# Circuit_Serial_3.net
KiCad netlist of a schematic drawn in EAGLE
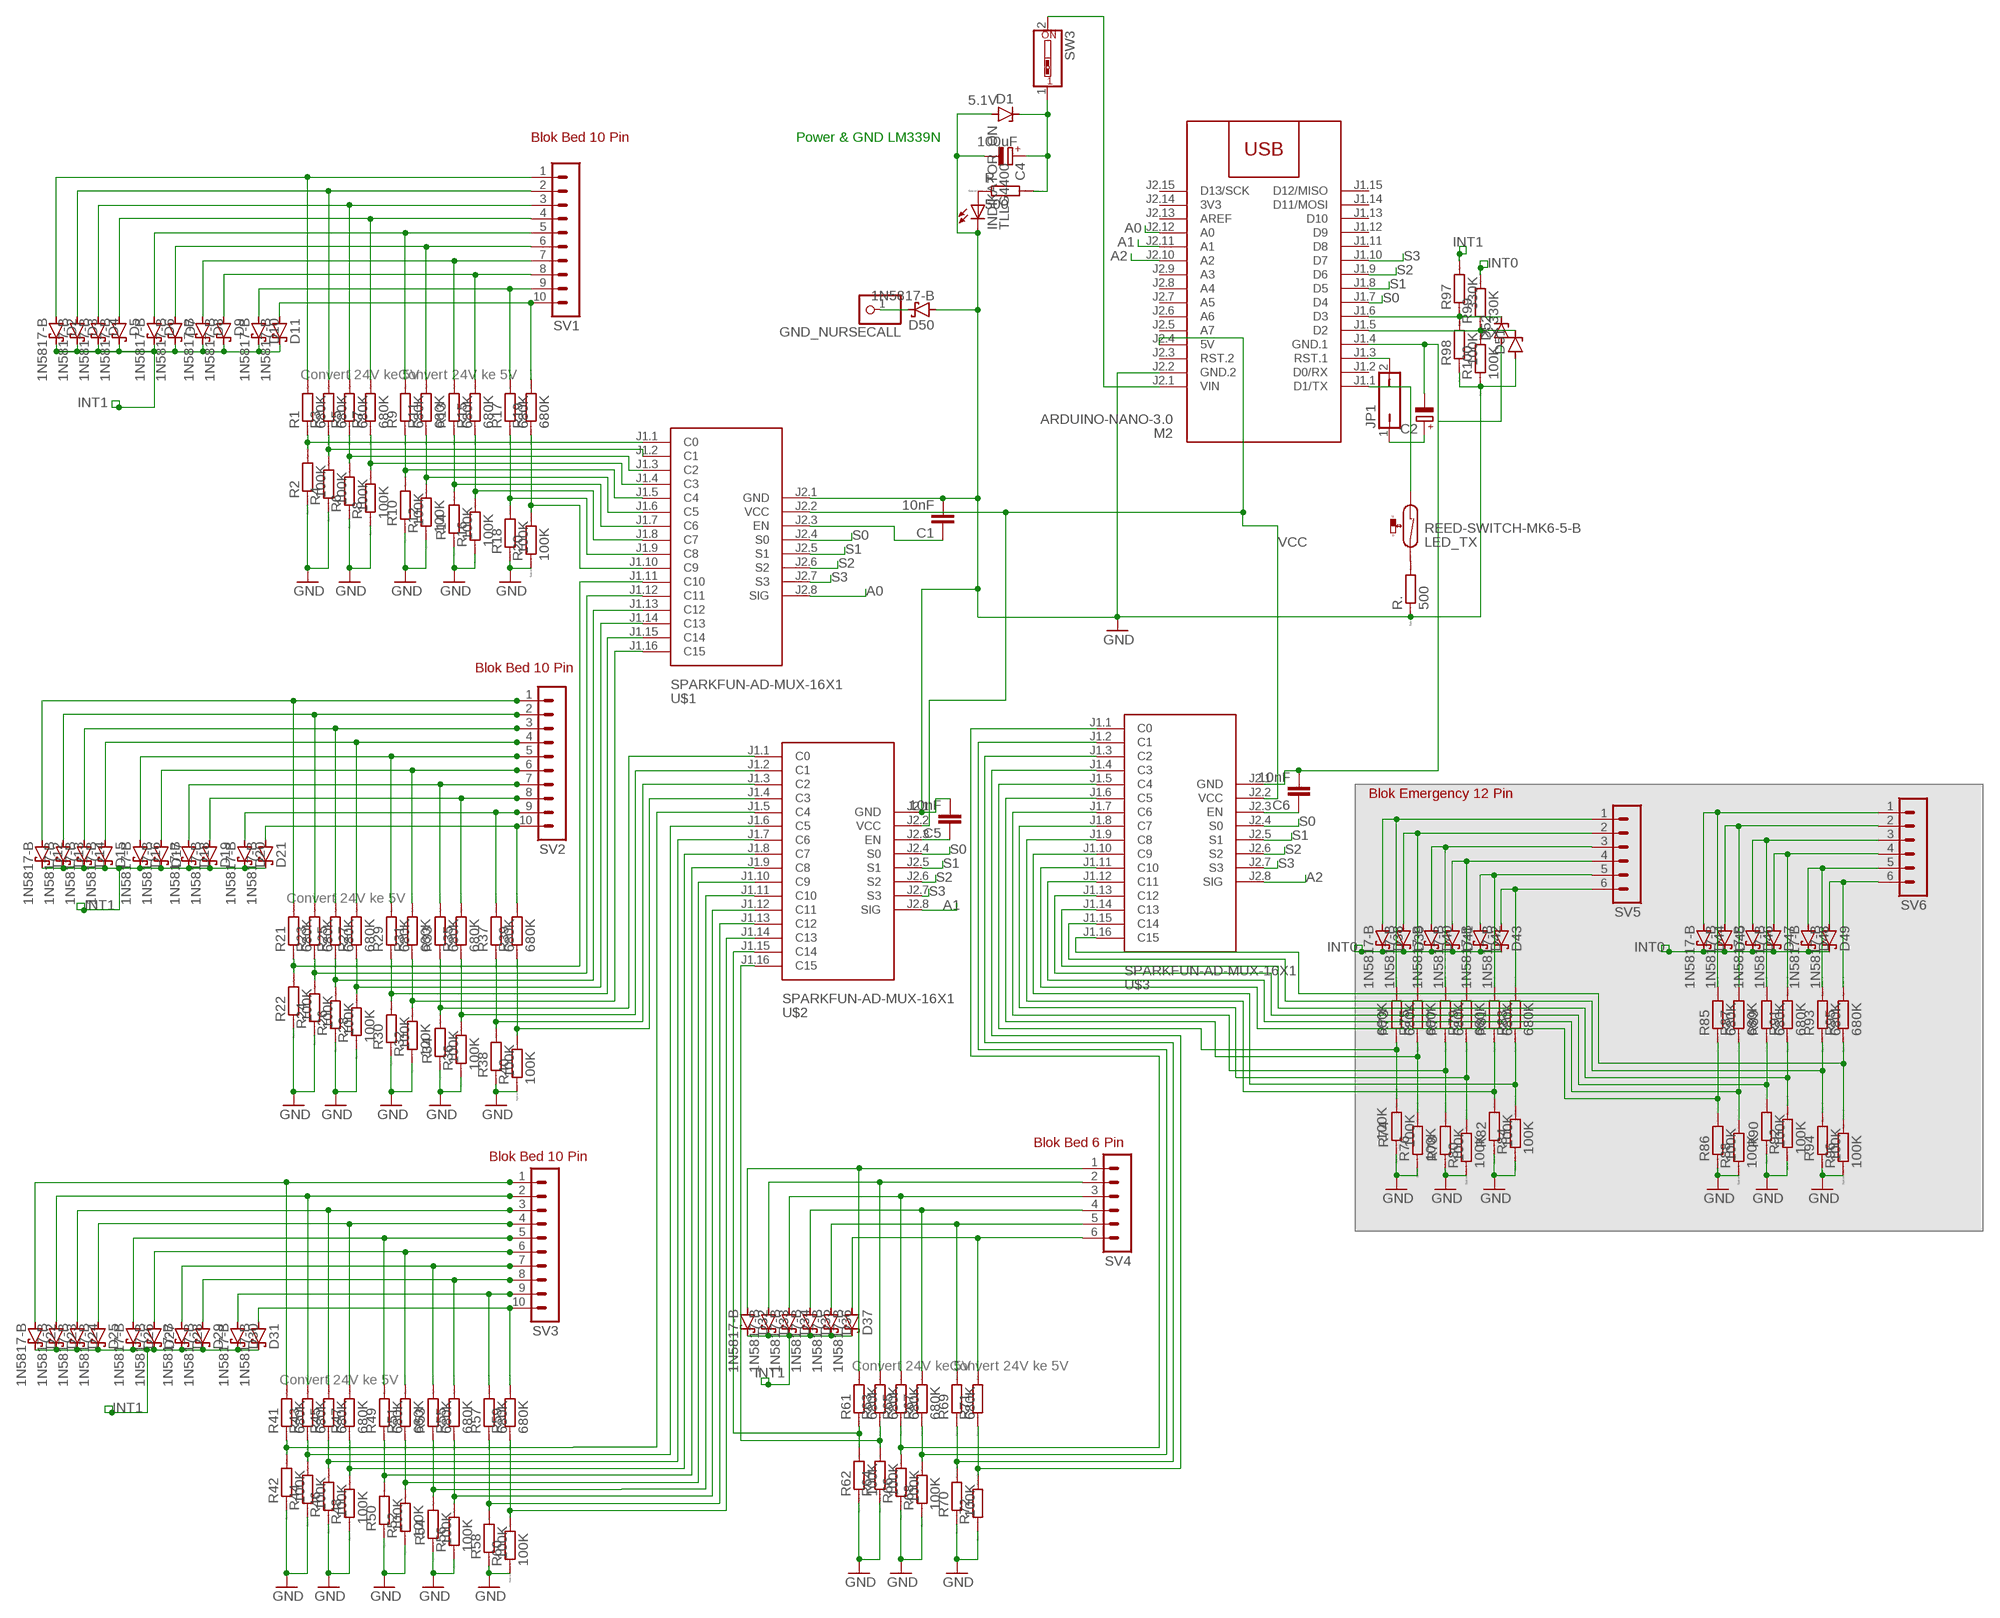
[diagram p0: schematic, sheet 1]

(export (version "E")
  (design (tool "Eeschema 10.0.6"))
  (components
    (comp (ref "C1")
      (value "10nF")
      (footprint "eagle-import:C025-030X050")
      (libsource (lib "eagle-import") (part "C-EU025-030X050"))
    )
    (comp (ref "C2")
      (value "CPOL-EUE3.5-8")
      (footprint "eagle-import:E3,5-8")
      (libsource (lib "eagle-import") (part "CPOL-EUE3.5-8"))
    )
    (comp (ref "C4")
      (value "100uF")
      (footprint "eagle-import:E3,5-10")
      (libsource (lib "eagle-import") (part "CPOL-EUE3.5-10"))
    )
    (comp (ref "C5")
      (value "10nF")
      (footprint "eagle-import:C025-030X050")
      (libsource (lib "eagle-import") (part "C-EU025-030X050"))
    )
    (comp (ref "C6")
      (value "10nF")
      (footprint "eagle-import:C025-030X050")
      (libsource (lib "eagle-import") (part "C-EU025-030X050"))
    )
    (comp (ref "D1")
      (value "5.1V")
      (footprint "eagle-import:DO34Z7")
      (libsource (lib "eagle-import") (part "ZENER-DIODEDO34-7"))
    )
    (comp (ref "D2")
      (value "1N5817-B")
      (footprint "eagle-import:DO41-7.6")
      (libsource (lib "eagle-import") (part "1N5817-B"))
    )
    (comp (ref "D3")
      (value "1N5817-B")
      (footprint "eagle-import:DO41-7.6")
      (libsource (lib "eagle-import") (part "1N5817-B"))
    )
    (comp (ref "D4")
      (value "1N5817-B")
      (footprint "eagle-import:DO41-7.6")
      (libsource (lib "eagle-import") (part "1N5817-B"))
    )
    (comp (ref "D5")
      (value "1N5817-B")
      (footprint "eagle-import:DO41-7.6")
      (libsource (lib "eagle-import") (part "1N5817-B"))
    )
    (comp (ref "D6")
      (value "1N5817-B")
      (footprint "eagle-import:DO41-7.6")
      (libsource (lib "eagle-import") (part "1N5817-B"))
    )
    (comp (ref "D7")
      (value "1N5817-B")
      (footprint "eagle-import:DO41-7.6")
      (libsource (lib "eagle-import") (part "1N5817-B"))
    )
    (comp (ref "D8")
      (value "1N5817-B")
      (footprint "eagle-import:DO41-7.6")
      (libsource (lib "eagle-import") (part "1N5817-B"))
    )
    (comp (ref "D9")
      (value "1N5817-B")
      (footprint "eagle-import:DO41-7.6")
      (libsource (lib "eagle-import") (part "1N5817-B"))
    )
    (comp (ref "D10")
      (value "1N5817-B")
      (footprint "eagle-import:DO41-7.6")
      (libsource (lib "eagle-import") (part "1N5817-B"))
    )
    (comp (ref "D11")
      (value "1N5817-B")
      (footprint "eagle-import:DO41-7.6")
      (libsource (lib "eagle-import") (part "1N5817-B"))
    )
    (comp (ref "D12")
      (value "1N5817-B")
      (footprint "eagle-import:DO41-7.6")
      (libsource (lib "eagle-import") (part "1N5817-B"))
    )
    (comp (ref "D13")
      (value "1N5817-B")
      (footprint "eagle-import:DO41-7.6")
      (libsource (lib "eagle-import") (part "1N5817-B"))
    )
    (comp (ref "D14")
      (value "1N5817-B")
      (footprint "eagle-import:DO41-7.6")
      (libsource (lib "eagle-import") (part "1N5817-B"))
    )
    (comp (ref "D15")
      (value "1N5817-B")
      (footprint "eagle-import:DO41-7.6")
      (libsource (lib "eagle-import") (part "1N5817-B"))
    )
    (comp (ref "D16")
      (value "1N5817-B")
      (footprint "eagle-import:DO41-7.6")
      (libsource (lib "eagle-import") (part "1N5817-B"))
    )
    (comp (ref "D17")
      (value "1N5817-B")
      (footprint "eagle-import:DO41-7.6")
      (libsource (lib "eagle-import") (part "1N5817-B"))
    )
    (comp (ref "D18")
      (value "1N5817-B")
      (footprint "eagle-import:DO41-7.6")
      (libsource (lib "eagle-import") (part "1N5817-B"))
    )
    (comp (ref "D19")
      (value "1N5817-B")
      (footprint "eagle-import:DO41-7.6")
      (libsource (lib "eagle-import") (part "1N5817-B"))
    )
    (comp (ref "D20")
      (value "1N5817-B")
      (footprint "eagle-import:DO41-7.6")
      (libsource (lib "eagle-import") (part "1N5817-B"))
    )
    (comp (ref "D21")
      (value "1N5817-B")
      (footprint "eagle-import:DO41-7.6")
      (libsource (lib "eagle-import") (part "1N5817-B"))
    )
    (comp (ref "D22")
      (value "1N5817-B")
      (footprint "eagle-import:DO41-7.6")
      (libsource (lib "eagle-import") (part "1N5817-B"))
    )
    (comp (ref "D23")
      (value "1N5817-B")
      (footprint "eagle-import:DO41-7.6")
      (libsource (lib "eagle-import") (part "1N5817-B"))
    )
    (comp (ref "D24")
      (value "1N5817-B")
      (footprint "eagle-import:DO41-7.6")
      (libsource (lib "eagle-import") (part "1N5817-B"))
    )
    (comp (ref "D25")
      (value "1N5817-B")
      (footprint "eagle-import:DO41-7.6")
      (libsource (lib "eagle-import") (part "1N5817-B"))
    )
    (comp (ref "D26")
      (value "1N5817-B")
      (footprint "eagle-import:DO41-7.6")
      (libsource (lib "eagle-import") (part "1N5817-B"))
    )
    (comp (ref "D27")
      (value "1N5817-B")
      (footprint "eagle-import:DO41-7.6")
      (libsource (lib "eagle-import") (part "1N5817-B"))
    )
    (comp (ref "D28")
      (value "1N5817-B")
      (footprint "eagle-import:DO41-7.6")
      (libsource (lib "eagle-import") (part "1N5817-B"))
    )
    (comp (ref "D29")
      (value "1N5817-B")
      (footprint "eagle-import:DO41-7.6")
      (libsource (lib "eagle-import") (part "1N5817-B"))
    )
    (comp (ref "D30")
      (value "1N5817-B")
      (footprint "eagle-import:DO41-7.6")
      (libsource (lib "eagle-import") (part "1N5817-B"))
    )
    (comp (ref "D31")
      (value "1N5817-B")
      (footprint "eagle-import:DO41-7.6")
      (libsource (lib "eagle-import") (part "1N5817-B"))
    )
    (comp (ref "D32")
      (value "1N5817-B")
      (footprint "eagle-import:DO41-7.6")
      (libsource (lib "eagle-import") (part "1N5817-B"))
    )
    (comp (ref "D33")
      (value "1N5817-B")
      (footprint "eagle-import:DO41-7.6")
      (libsource (lib "eagle-import") (part "1N5817-B"))
    )
    (comp (ref "D34")
      (value "1N5817-B")
      (footprint "eagle-import:DO41-7.6")
      (libsource (lib "eagle-import") (part "1N5817-B"))
    )
    (comp (ref "D35")
      (value "1N5817-B")
      (footprint "eagle-import:DO41-7.6")
      (libsource (lib "eagle-import") (part "1N5817-B"))
    )
    (comp (ref "D36")
      (value "1N5817-B")
      (footprint "eagle-import:DO41-7.6")
      (libsource (lib "eagle-import") (part "1N5817-B"))
    )
    (comp (ref "D37")
      (value "1N5817-B")
      (footprint "eagle-import:DO41-7.6")
      (libsource (lib "eagle-import") (part "1N5817-B"))
    )
    (comp (ref "D38")
      (value "1N5817-B")
      (footprint "eagle-import:DO41-7.6")
      (libsource (lib "eagle-import") (part "1N5817-B"))
    )
    (comp (ref "D39")
      (value "1N5817-B")
      (footprint "eagle-import:DO41-7.6")
      (libsource (lib "eagle-import") (part "1N5817-B"))
    )
    (comp (ref "D40")
      (value "1N5817-B")
      (footprint "eagle-import:DO41-7.6")
      (libsource (lib "eagle-import") (part "1N5817-B"))
    )
    (comp (ref "D41")
      (value "1N5817-B")
      (footprint "eagle-import:DO41-7.6")
      (libsource (lib "eagle-import") (part "1N5817-B"))
    )
    (comp (ref "D42")
      (value "1N5817-B")
      (footprint "eagle-import:DO41-7.6")
      (libsource (lib "eagle-import") (part "1N5817-B"))
    )
    (comp (ref "D43")
      (value "1N5817-B")
      (footprint "eagle-import:DO41-7.6")
      (libsource (lib "eagle-import") (part "1N5817-B"))
    )
    (comp (ref "D44")
      (value "1N5817-B")
      (footprint "eagle-import:DO41-7.6")
      (libsource (lib "eagle-import") (part "1N5817-B"))
    )
    (comp (ref "D45")
      (value "1N5817-B")
      (footprint "eagle-import:DO41-7.6")
      (libsource (lib "eagle-import") (part "1N5817-B"))
    )
    (comp (ref "D46")
      (value "1N5817-B")
      (footprint "eagle-import:DO41-7.6")
      (libsource (lib "eagle-import") (part "1N5817-B"))
    )
    (comp (ref "D47")
      (value "1N5817-B")
      (footprint "eagle-import:DO41-7.6")
      (libsource (lib "eagle-import") (part "1N5817-B"))
    )
    (comp (ref "D48")
      (value "1N5817-B")
      (footprint "eagle-import:DO41-7.6")
      (libsource (lib "eagle-import") (part "1N5817-B"))
    )
    (comp (ref "D49")
      (value "1N5817-B")
      (footprint "eagle-import:DO41-7.6")
      (libsource (lib "eagle-import") (part "1N5817-B"))
    )
    (comp (ref "D50")
      (value "1N5817-B")
      (footprint "eagle-import:DO41-7.6")
      (libsource (lib "eagle-import") (part "1N5817-B"))
    )
    (comp (ref "D51")
      (value "ZENER-DIODEDO34-7")
      (footprint "eagle-import:DO34Z7")
      (libsource (lib "eagle-import") (part "ZENER-DIODEDO34-7"))
    )
    (comp (ref "D52")
      (value "ZENER-DIODEDO34-7")
      (footprint "eagle-import:DO34Z7")
      (libsource (lib "eagle-import") (part "ZENER-DIODEDO34-7"))
    )
    (comp (ref "GND_NURSECALL")
      (value "PINHD-1X1")
      (footprint "eagle-import:1X01")
      (libsource (lib "eagle-import") (part "PINHD-1X1"))
    )
    (comp (ref "INDIKATOR_ON")
      (value "TLLG4400")
      (footprint "eagle-import:LED3MM")
      (fields (field (name "MF") "VISHAY SEMICONDUCTOR"))
      (libsource (lib "eagle-import") (part "TLLG4400"))
    )
    (comp (ref "JP1")
      (value "JP1Q")
      (footprint "eagle-import:JP1")
      (libsource (lib "eagle-import") (part "JP1Q"))
    )
    (comp (ref "LED_TX")
      (value "REED-SWITCH-MK6-5-B")
      (footprint "eagle-import:MK6-5")
      (fields (field (name "MF") "MEDER") (field (name "MPN") "MK6-5-B"))
      (libsource (lib "eagle-import") (part "REED-SWITCH-MK6-5-B"))
    )
    (comp (ref "M2")
      (value "ARDUINO-NANO-3.0")
      (footprint "eagle-import:ARDUINO-NANO-3.0")
      (libsource (lib "eagle-import") (part "ARDUINO-NANO-3.0"))
    )
    (comp (ref "R")
      (value "500")
      (footprint "eagle-import:0204_7")
      (libsource (lib "eagle-import") (part "R0204/7"))
    )
    (comp (ref "R.")
      (value "500")
      (footprint "eagle-import:0204_7")
      (libsource (lib "eagle-import") (part "R0204/7"))
    )
    (comp (ref "R1")
      (value "680K")
      (footprint "eagle-import:0204_7")
      (libsource (lib "eagle-import") (part "R0204/7"))
    )
    (comp (ref "R2")
      (value "100K")
      (footprint "eagle-import:0204_7")
      (libsource (lib "eagle-import") (part "R0204/7"))
    )
    (comp (ref "R3")
      (value "680K")
      (footprint "eagle-import:0204_7")
      (libsource (lib "eagle-import") (part "R0204/7"))
    )
    (comp (ref "R4")
      (value "100K")
      (footprint "eagle-import:0204_7")
      (libsource (lib "eagle-import") (part "R0204/7"))
    )
    (comp (ref "R5")
      (value "680K")
      (footprint "eagle-import:0204_7")
      (libsource (lib "eagle-import") (part "R0204/7"))
    )
    (comp (ref "R6")
      (value "100K")
      (footprint "eagle-import:0204_7")
      (libsource (lib "eagle-import") (part "R0204/7"))
    )
    (comp (ref "R7")
      (value "680K")
      (footprint "eagle-import:0204_7")
      (libsource (lib "eagle-import") (part "R0204/7"))
    )
    (comp (ref "R8")
      (value "100K")
      (footprint "eagle-import:0204_7")
      (libsource (lib "eagle-import") (part "R0204/7"))
    )
    (comp (ref "R9")
      (value "680K")
      (footprint "eagle-import:0204_7")
      (libsource (lib "eagle-import") (part "R0204/7"))
    )
    (comp (ref "R10")
      (value "100K")
      (footprint "eagle-import:0204_7")
      (libsource (lib "eagle-import") (part "R0204/7"))
    )
    (comp (ref "R11")
      (value "680K")
      (footprint "eagle-import:0204_7")
      (libsource (lib "eagle-import") (part "R0204/7"))
    )
    (comp (ref "R12")
      (value "100K")
      (footprint "eagle-import:0204_7")
      (libsource (lib "eagle-import") (part "R0204/7"))
    )
    (comp (ref "R13")
      (value "680K")
      (footprint "eagle-import:0204_7")
      (libsource (lib "eagle-import") (part "R0204/7"))
    )
    (comp (ref "R14")
      (value "100K")
      (footprint "eagle-import:0204_7")
      (libsource (lib "eagle-import") (part "R0204/7"))
    )
    (comp (ref "R15")
      (value "680K")
      (footprint "eagle-import:0204_7")
      (libsource (lib "eagle-import") (part "R0204/7"))
    )
    (comp (ref "R16")
      (value "100K")
      (footprint "eagle-import:0204_7")
      (libsource (lib "eagle-import") (part "R0204/7"))
    )
    (comp (ref "R17")
      (value "680K")
      (footprint "eagle-import:0204_7")
      (libsource (lib "eagle-import") (part "R0204/7"))
    )
    (comp (ref "R18")
      (value "100K")
      (footprint "eagle-import:0204_7")
      (libsource (lib "eagle-import") (part "R0204/7"))
    )
    (comp (ref "R19")
      (value "680K")
      (footprint "eagle-import:0204_7")
      (libsource (lib "eagle-import") (part "R0204/7"))
    )
    (comp (ref "R20")
      (value "100K")
      (footprint "eagle-import:0204_7")
      (libsource (lib "eagle-import") (part "R0204/7"))
    )
    (comp (ref "R21")
      (value "680K")
      (footprint "eagle-import:0204_7")
      (libsource (lib "eagle-import") (part "R0204/7"))
    )
    (comp (ref "R22")
      (value "100K")
      (footprint "eagle-import:0204_7")
      (libsource (lib "eagle-import") (part "R0204/7"))
    )
    (comp (ref "R23")
      (value "680K")
      (footprint "eagle-import:0204_7")
      (libsource (lib "eagle-import") (part "R0204/7"))
    )
    (comp (ref "R24")
      (value "100K")
      (footprint "eagle-import:0204_7")
      (libsource (lib "eagle-import") (part "R0204/7"))
    )
    (comp (ref "R25")
      (value "680K")
      (footprint "eagle-import:0204_7")
      (libsource (lib "eagle-import") (part "R0204/7"))
    )
    (comp (ref "R26")
      (value "100K")
      (footprint "eagle-import:0204_7")
      (libsource (lib "eagle-import") (part "R0204/7"))
    )
    (comp (ref "R27")
      (value "680K")
      (footprint "eagle-import:0204_7")
      (libsource (lib "eagle-import") (part "R0204/7"))
    )
    (comp (ref "R28")
      (value "100K")
      (footprint "eagle-import:0204_7")
      (libsource (lib "eagle-import") (part "R0204/7"))
    )
    (comp (ref "R29")
      (value "680K")
      (footprint "eagle-import:0204_7")
      (libsource (lib "eagle-import") (part "R0204/7"))
    )
    (comp (ref "R30")
      (value "100K")
      (footprint "eagle-import:0204_7")
      (libsource (lib "eagle-import") (part "R0204/7"))
    )
    (comp (ref "R31")
      (value "680K")
      (footprint "eagle-import:0204_7")
      (libsource (lib "eagle-import") (part "R0204/7"))
    )
    (comp (ref "R32")
      (value "100K")
      (footprint "eagle-import:0204_7")
      (libsource (lib "eagle-import") (part "R0204/7"))
    )
    (comp (ref "R33")
      (value "680K")
      (footprint "eagle-import:0204_7")
      (libsource (lib "eagle-import") (part "R0204/7"))
    )
    (comp (ref "R34")
      (value "100K")
      (footprint "eagle-import:0204_7")
      (libsource (lib "eagle-import") (part "R0204/7"))
    )
    (comp (ref "R35")
      (value "680K")
      (footprint "eagle-import:0204_7")
      (libsource (lib "eagle-import") (part "R0204/7"))
    )
    (comp (ref "R36")
      (value "100K")
      (footprint "eagle-import:0204_7")
      (libsource (lib "eagle-import") (part "R0204/7"))
    )
    (comp (ref "R37")
      (value "680K")
      (footprint "eagle-import:0204_7")
      (libsource (lib "eagle-import") (part "R0204/7"))
    )
    (comp (ref "R38")
      (value "100K")
      (footprint "eagle-import:0204_7")
      (libsource (lib "eagle-import") (part "R0204/7"))
    )
    (comp (ref "R39")
      (value "680K")
      (footprint "eagle-import:0204_7")
      (libsource (lib "eagle-import") (part "R0204/7"))
    )
    (comp (ref "R40")
      (value "100K")
      (footprint "eagle-import:0204_7")
      (libsource (lib "eagle-import") (part "R0204/7"))
    )
    (comp (ref "R41")
      (value "680K")
      (footprint "eagle-import:0204_7")
      (libsource (lib "eagle-import") (part "R0204/7"))
    )
    (comp (ref "R42")
      (value "100K")
      (footprint "eagle-import:0204_7")
      (libsource (lib "eagle-import") (part "R0204/7"))
    )
    (comp (ref "R43")
      (value "680K")
      (footprint "eagle-import:0204_7")
      (libsource (lib "eagle-import") (part "R0204/7"))
    )
    (comp (ref "R44")
      (value "100K")
      (footprint "eagle-import:0204_7")
      (libsource (lib "eagle-import") (part "R0204/7"))
    )
    (comp (ref "R45")
      (value "680K")
      (footprint "eagle-import:0204_7")
      (libsource (lib "eagle-import") (part "R0204/7"))
    )
    (comp (ref "R46")
      (value "100K")
      (footprint "eagle-import:0204_7")
      (libsource (lib "eagle-import") (part "R0204/7"))
    )
    (comp (ref "R47")
      (value "680K")
      (footprint "eagle-import:0204_7")
      (libsource (lib "eagle-import") (part "R0204/7"))
    )
    (comp (ref "R48")
      (value "100K")
      (footprint "eagle-import:0204_7")
      (libsource (lib "eagle-import") (part "R0204/7"))
    )
    (comp (ref "R49")
      (value "680K")
      (footprint "eagle-import:0204_7")
      (libsource (lib "eagle-import") (part "R0204/7"))
    )
    (comp (ref "R50")
      (value "100K")
      (footprint "eagle-import:0204_7")
      (libsource (lib "eagle-import") (part "R0204/7"))
    )
    (comp (ref "R51")
      (value "680K")
      (footprint "eagle-import:0204_7")
      (libsource (lib "eagle-import") (part "R0204/7"))
    )
    (comp (ref "R52")
      (value "100K")
      (footprint "eagle-import:0204_7")
      (libsource (lib "eagle-import") (part "R0204/7"))
    )
    (comp (ref "R53")
      (value "680K")
      (footprint "eagle-import:0204_7")
      (libsource (lib "eagle-import") (part "R0204/7"))
    )
    (comp (ref "R54")
      (value "100K")
      (footprint "eagle-import:0204_7")
      (libsource (lib "eagle-import") (part "R0204/7"))
    )
    (comp (ref "R55")
      (value "680K")
      (footprint "eagle-import:0204_7")
      (libsource (lib "eagle-import") (part "R0204/7"))
    )
    (comp (ref "R56")
      (value "100K")
      (footprint "eagle-import:0204_7")
      (libsource (lib "eagle-import") (part "R0204/7"))
    )
    (comp (ref "R57")
      (value "680K")
      (footprint "eagle-import:0204_7")
      (libsource (lib "eagle-import") (part "R0204/7"))
    )
    (comp (ref "R58")
      (value "100K")
      (footprint "eagle-import:0204_7")
      (libsource (lib "eagle-import") (part "R0204/7"))
    )
    (comp (ref "R59")
      (value "680K")
      (footprint "eagle-import:0204_7")
      (libsource (lib "eagle-import") (part "R0204/7"))
    )
    (comp (ref "R60")
      (value "100K")
      (footprint "eagle-import:0204_7")
      (libsource (lib "eagle-import") (part "R0204/7"))
    )
    (comp (ref "R61")
      (value "680K")
      (footprint "eagle-import:0204_7")
      (libsource (lib "eagle-import") (part "R0204/7"))
    )
    (comp (ref "R62")
      (value "100K")
      (footprint "eagle-import:0204_7")
      (libsource (lib "eagle-import") (part "R0204/7"))
    )
    (comp (ref "R63")
      (value "680K")
      (footprint "eagle-import:0204_7")
      (libsource (lib "eagle-import") (part "R0204/7"))
    )
    (comp (ref "R64")
      (value "100K")
      (footprint "eagle-import:0204_7")
      (libsource (lib "eagle-import") (part "R0204/7"))
    )
    (comp (ref "R65")
      (value "680K")
      (footprint "eagle-import:0204_7")
      (libsource (lib "eagle-import") (part "R0204/7"))
    )
    (comp (ref "R66")
      (value "100K")
      (footprint "eagle-import:0204_7")
      (libsource (lib "eagle-import") (part "R0204/7"))
    )
    (comp (ref "R67")
      (value "680K")
      (footprint "eagle-import:0204_7")
      (libsource (lib "eagle-import") (part "R0204/7"))
    )
    (comp (ref "R68")
      (value "100K")
      (footprint "eagle-import:0204_7")
      (libsource (lib "eagle-import") (part "R0204/7"))
    )
    (comp (ref "R69")
      (value "680K")
      (footprint "eagle-import:0204_7")
      (libsource (lib "eagle-import") (part "R0204/7"))
    )
    (comp (ref "R70")
      (value "100K")
      (footprint "eagle-import:0204_7")
      (libsource (lib "eagle-import") (part "R0204/7"))
    )
    (comp (ref "R71")
      (value "680K")
      (footprint "eagle-import:0204_7")
      (libsource (lib "eagle-import") (part "R0204/7"))
    )
    (comp (ref "R72")
      (value "100K")
      (footprint "eagle-import:0204_7")
      (libsource (lib "eagle-import") (part "R0204/7"))
    )
    (comp (ref "R73")
      (value "680K")
      (footprint "eagle-import:0204_7")
      (libsource (lib "eagle-import") (part "R0204/7"))
    )
    (comp (ref "R74")
      (value "100K")
      (footprint "eagle-import:0204_7")
      (libsource (lib "eagle-import") (part "R0204/7"))
    )
    (comp (ref "R75")
      (value "680K")
      (footprint "eagle-import:0204_7")
      (libsource (lib "eagle-import") (part "R0204/7"))
    )
    (comp (ref "R76")
      (value "100K")
      (footprint "eagle-import:0204_7")
      (libsource (lib "eagle-import") (part "R0204/7"))
    )
    (comp (ref "R77")
      (value "680K")
      (footprint "eagle-import:0204_7")
      (libsource (lib "eagle-import") (part "R0204/7"))
    )
    (comp (ref "R78")
      (value "100K")
      (footprint "eagle-import:0204_7")
      (libsource (lib "eagle-import") (part "R0204/7"))
    )
    (comp (ref "R79")
      (value "680K")
      (footprint "eagle-import:0204_7")
      (libsource (lib "eagle-import") (part "R0204/7"))
    )
    (comp (ref "R80")
      (value "100K")
      (footprint "eagle-import:0204_7")
      (libsource (lib "eagle-import") (part "R0204/7"))
    )
    (comp (ref "R81")
      (value "680K")
      (footprint "eagle-import:0204_7")
      (libsource (lib "eagle-import") (part "R0204/7"))
    )
    (comp (ref "R82")
      (value "100K")
      (footprint "eagle-import:0204_7")
      (libsource (lib "eagle-import") (part "R0204/7"))
    )
    (comp (ref "R83")
      (value "680K")
      (footprint "eagle-import:0204_7")
      (libsource (lib "eagle-import") (part "R0204/7"))
    )
    (comp (ref "R84")
      (value "100K")
      (footprint "eagle-import:0204_7")
      (libsource (lib "eagle-import") (part "R0204/7"))
    )
    (comp (ref "R85")
      (value "680K")
      (footprint "eagle-import:0204_7")
      (libsource (lib "eagle-import") (part "R0204/7"))
    )
    (comp (ref "R86")
      (value "100K")
      (footprint "eagle-import:0204_7")
      (libsource (lib "eagle-import") (part "R0204/7"))
    )
    (comp (ref "R87")
      (value "680K")
      (footprint "eagle-import:0204_7")
      (libsource (lib "eagle-import") (part "R0204/7"))
    )
    (comp (ref "R88")
      (value "100K")
      (footprint "eagle-import:0204_7")
      (libsource (lib "eagle-import") (part "R0204/7"))
    )
    (comp (ref "R89")
      (value "680K")
      (footprint "eagle-import:0204_7")
      (libsource (lib "eagle-import") (part "R0204/7"))
    )
    (comp (ref "R90")
      (value "100K")
      (footprint "eagle-import:0204_7")
      (libsource (lib "eagle-import") (part "R0204/7"))
    )
    (comp (ref "R91")
      (value "680K")
      (footprint "eagle-import:0204_7")
      (libsource (lib "eagle-import") (part "R0204/7"))
    )
    (comp (ref "R92")
      (value "100K")
      (footprint "eagle-import:0204_7")
      (libsource (lib "eagle-import") (part "R0204/7"))
    )
    (comp (ref "R93")
      (value "680K")
      (footprint "eagle-import:0204_7")
      (libsource (lib "eagle-import") (part "R0204/7"))
    )
    (comp (ref "R94")
      (value "100K")
      (footprint "eagle-import:0204_7")
      (libsource (lib "eagle-import") (part "R0204/7"))
    )
    (comp (ref "R95")
      (value "680K")
      (footprint "eagle-import:0204_7")
      (libsource (lib "eagle-import") (part "R0204/7"))
    )
    (comp (ref "R96")
      (value "100K")
      (footprint "eagle-import:0204_7")
      (libsource (lib "eagle-import") (part "R0204/7"))
    )
    (comp (ref "R97")
      (value "330K")
      (footprint "eagle-import:0204_7")
      (libsource (lib "eagle-import") (part "R0204/7"))
    )
    (comp (ref "R98")
      (value "100K")
      (footprint "eagle-import:0204_7")
      (libsource (lib "eagle-import") (part "R0204/7"))
    )
    (comp (ref "R99")
      (value "330K")
      (footprint "eagle-import:0204_7")
      (libsource (lib "eagle-import") (part "R0204/7"))
    )
    (comp (ref "R100")
      (value "100K")
      (footprint "eagle-import:0204_7")
      (libsource (lib "eagle-import") (part "R0204/7"))
    )
    (comp (ref "SV1")
      (value "MA10-1W")
      (footprint "eagle-import:MA10-1W")
      (libsource (lib "eagle-import") (part "MA10-1W"))
    )
    (comp (ref "SV2")
      (value "MA10-1W")
      (footprint "eagle-import:MA10-1W")
      (libsource (lib "eagle-import") (part "MA10-1W"))
    )
    (comp (ref "SV3")
      (value "MA10-1W")
      (footprint "eagle-import:MA10-1W")
      (libsource (lib "eagle-import") (part "MA10-1W"))
    )
    (comp (ref "SV4")
      (value "MA06-1")
      (footprint "eagle-import:MA06-1")
      (libsource (lib "eagle-import") (part "MA06-1"))
    )
    (comp (ref "SV5")
      (value "MA06-1")
      (footprint "eagle-import:MA06-1")
      (libsource (lib "eagle-import") (part "MA06-1"))
    )
    (comp (ref "SV6")
      (value "MA06-1")
      (footprint "eagle-import:MA06-1")
      (libsource (lib "eagle-import") (part "MA06-1"))
    )
    (comp (ref "SW3")
      (value "SW_DIP-1")
      (footprint "eagle-import:EDG-01")
      (libsource (lib "eagle-import") (part "SW_DIP-1"))
    )
    (comp (ref "U$1")
      (value "SPARKFUN-AD-MUX-16X1")
      (footprint "eagle-import:SPARKFUN-AD-MUX-16X1")
      (libsource (lib "eagle-import") (part "SPARKFUN-AD-MUX-16X1"))
    )
    (comp (ref "U$2")
      (value "SPARKFUN-AD-MUX-16X1")
      (footprint "eagle-import:SPARKFUN-AD-MUX-16X1")
      (libsource (lib "eagle-import") (part "SPARKFUN-AD-MUX-16X1"))
    )
    (comp (ref "U$3")
      (value "SPARKFUN-AD-MUX-16X1")
      (footprint "eagle-import:SPARKFUN-AD-MUX-16X1")
      (libsource (lib "eagle-import") (part "SPARKFUN-AD-MUX-16X1"))
    )
  )
  (nets
    (net (code "1") (name "/3V3") (class "Default")
      (node (ref "M2") (pin "J2.14") (pinfunction "3V3_J2.14") (pintype "power_in"))
    )
    (net (code "2") (name "/A0") (class "Default")
      (node (ref "M2") (pin "J2.12") (pinfunction "A0_J2.12") (pintype "bidirectional"))
      (node (ref "U$1") (pin "J2.8") (pinfunction "SIG_J2.8") (pintype "bidirectional"))
    )
    (net (code "3") (name "/A1") (class "Default")
      (node (ref "M2") (pin "J2.11") (pinfunction "A1_J2.11") (pintype "bidirectional"))
      (node (ref "U$2") (pin "J2.8") (pinfunction "SIG_J2.8") (pintype "bidirectional"))
    )
    (net (code "4") (name "/A2") (class "Default")
      (node (ref "M2") (pin "J2.10") (pinfunction "A2_J2.10") (pintype "bidirectional"))
      (node (ref "U$3") (pin "J2.8") (pinfunction "SIG_J2.8") (pintype "bidirectional"))
    )
    (net (code "5") (name "/INT0") (class "Default")
      (node (ref "D38") (pin "C") (pinfunction "C_C") (pintype "passive"))
      (node (ref "D39") (pin "C") (pinfunction "C_C") (pintype "passive"))
      (node (ref "D40") (pin "C") (pinfunction "C_C") (pintype "passive"))
      (node (ref "D41") (pin "C") (pinfunction "C_C") (pintype "passive"))
      (node (ref "D42") (pin "C") (pinfunction "C_C") (pintype "passive"))
      (node (ref "D43") (pin "C") (pinfunction "C_C") (pintype "passive"))
      (node (ref "D44") (pin "C") (pinfunction "C_C") (pintype "passive"))
      (node (ref "D45") (pin "C") (pinfunction "C_C") (pintype "passive"))
      (node (ref "D46") (pin "C") (pinfunction "C_C") (pintype "passive"))
      (node (ref "D47") (pin "C") (pinfunction "C_C") (pintype "passive"))
      (node (ref "D48") (pin "C") (pinfunction "C_C") (pintype "passive"))
      (node (ref "D49") (pin "C") (pinfunction "C_C") (pintype "passive"))
      (node (ref "R99") (pin "2") (pinfunction "2_2") (pintype "passive"))
    )
    (net (code "6") (name "/INT1") (class "Default")
      (node (ref "D10") (pin "C") (pinfunction "C_C") (pintype "passive"))
      (node (ref "D11") (pin "C") (pinfunction "C_C") (pintype "passive"))
      (node (ref "D12") (pin "C") (pinfunction "C_C") (pintype "passive"))
      (node (ref "D13") (pin "C") (pinfunction "C_C") (pintype "passive"))
      (node (ref "D14") (pin "C") (pinfunction "C_C") (pintype "passive"))
      (node (ref "D15") (pin "C") (pinfunction "C_C") (pintype "passive"))
      (node (ref "D16") (pin "C") (pinfunction "C_C") (pintype "passive"))
      (node (ref "D17") (pin "C") (pinfunction "C_C") (pintype "passive"))
      (node (ref "D18") (pin "C") (pinfunction "C_C") (pintype "passive"))
      (node (ref "D19") (pin "C") (pinfunction "C_C") (pintype "passive"))
      (node (ref "D2") (pin "C") (pinfunction "C_C") (pintype "passive"))
      (node (ref "D20") (pin "C") (pinfunction "C_C") (pintype "passive"))
      (node (ref "D21") (pin "C") (pinfunction "C_C") (pintype "passive"))
      (node (ref "D22") (pin "C") (pinfunction "C_C") (pintype "passive"))
      (node (ref "D23") (pin "C") (pinfunction "C_C") (pintype "passive"))
      (node (ref "D24") (pin "C") (pinfunction "C_C") (pintype "passive"))
      (node (ref "D25") (pin "C") (pinfunction "C_C") (pintype "passive"))
      (node (ref "D26") (pin "C") (pinfunction "C_C") (pintype "passive"))
      (node (ref "D27") (pin "C") (pinfunction "C_C") (pintype "passive"))
      (node (ref "D28") (pin "C") (pinfunction "C_C") (pintype "passive"))
      (node (ref "D29") (pin "C") (pinfunction "C_C") (pintype "passive"))
      (node (ref "D3") (pin "C") (pinfunction "C_C") (pintype "passive"))
      (node (ref "D30") (pin "C") (pinfunction "C_C") (pintype "passive"))
      (node (ref "D31") (pin "C") (pinfunction "C_C") (pintype "passive"))
      (node (ref "D32") (pin "C") (pinfunction "C_C") (pintype "passive"))
      (node (ref "D33") (pin "C") (pinfunction "C_C") (pintype "passive"))
      (node (ref "D34") (pin "C") (pinfunction "C_C") (pintype "passive"))
      (node (ref "D35") (pin "C") (pinfunction "C_C") (pintype "passive"))
      (node (ref "D36") (pin "C") (pinfunction "C_C") (pintype "passive"))
      (node (ref "D37") (pin "C") (pinfunction "C_C") (pintype "passive"))
      (node (ref "D4") (pin "C") (pinfunction "C_C") (pintype "passive"))
      (node (ref "D5") (pin "C") (pinfunction "C_C") (pintype "passive"))
      (node (ref "D6") (pin "C") (pinfunction "C_C") (pintype "passive"))
      (node (ref "D7") (pin "C") (pinfunction "C_C") (pintype "passive"))
      (node (ref "D8") (pin "C") (pinfunction "C_C") (pintype "passive"))
      (node (ref "D9") (pin "C") (pinfunction "C_C") (pintype "passive"))
      (node (ref "R97") (pin "2") (pinfunction "2_2") (pintype "passive"))
    )
    (net (code "7") (name "/S0") (class "Default")
      (node (ref "M2") (pin "J1.7") (pinfunction "D4_J1.7") (pintype "bidirectional"))
      (node (ref "U$1") (pin "J2.4") (pinfunction "S0_J2.4") (pintype "bidirectional"))
      (node (ref "U$2") (pin "J2.4") (pinfunction "S0_J2.4") (pintype "bidirectional"))
      (node (ref "U$3") (pin "J2.4") (pinfunction "S0_J2.4") (pintype "bidirectional"))
    )
    (net (code "8") (name "/S1") (class "Default")
      (node (ref "M2") (pin "J1.8") (pinfunction "D5_J1.8") (pintype "bidirectional"))
      (node (ref "U$1") (pin "J2.5") (pinfunction "S1_J2.5") (pintype "bidirectional"))
      (node (ref "U$2") (pin "J2.5") (pinfunction "S1_J2.5") (pintype "bidirectional"))
      (node (ref "U$3") (pin "J2.5") (pinfunction "S1_J2.5") (pintype "bidirectional"))
    )
    (net (code "9") (name "/S2") (class "Default")
      (node (ref "M2") (pin "J1.9") (pinfunction "D6_J1.9") (pintype "bidirectional"))
      (node (ref "U$1") (pin "J2.6") (pinfunction "S2_J2.6") (pintype "bidirectional"))
      (node (ref "U$2") (pin "J2.6") (pinfunction "S2_J2.6") (pintype "bidirectional"))
      (node (ref "U$3") (pin "J2.6") (pinfunction "S2_J2.6") (pintype "bidirectional"))
    )
    (net (code "10") (name "/S3") (class "Default")
      (node (ref "M2") (pin "J1.10") (pinfunction "D7_J1.10") (pintype "bidirectional"))
      (node (ref "U$1") (pin "J2.7") (pinfunction "S3_J2.7") (pintype "bidirectional"))
      (node (ref "U$2") (pin "J2.7") (pinfunction "S3_J2.7") (pintype "bidirectional"))
      (node (ref "U$3") (pin "J2.7") (pinfunction "S3_J2.7") (pintype "bidirectional"))
    )
    (net (code "11") (name "/VCC") (class "Default")
      (node (ref "M2") (pin "J2.4") (pinfunction "5V_J2.4") (pintype "power_in"))
      (node (ref "U$1") (pin "J2.2") (pinfunction "VCC_J2.2") (pintype "power_in"))
      (node (ref "U$2") (pin "J2.2") (pinfunction "VCC_J2.2") (pintype "power_in"))
      (node (ref "U$3") (pin "J2.2") (pinfunction "VCC_J2.2") (pintype "power_in"))
    )
    (net (code "12") (name "/XX") (class "Default")
      (node (ref "D51") (pin "C") (pinfunction "C_C") (pintype "passive"))
      (node (ref "M2") (pin "J1.5") (pinfunction "D2_J1.5") (pintype "bidirectional"))
      (node (ref "R100") (pin "2") (pinfunction "2_2") (pintype "passive"))
      (node (ref "R99") (pin "1") (pinfunction "1_1") (pintype "passive"))
    )
    (net (code "13") (name "GND") (class "Default")
      (node (ref "C1") (pin "2") (pinfunction "2_2") (pintype "passive"))
      (node (ref "C4") (pin "-") (pinfunction "-_-") (pintype "passive"))
      (node (ref "C5") (pin "2") (pinfunction "2_2") (pintype "passive"))
      (node (ref "D1") (pin "A") (pinfunction "A_A") (pintype "passive"))
      (node (ref "D50") (pin "A") (pinfunction "A_A") (pintype "passive"))
      (node (ref "D51") (pin "A") (pinfunction "A_A") (pintype "passive"))
      (node (ref "INDIKATOR_ON") (pin "K") (pinfunction "C_K") (pintype "passive"))
      (node (ref "M2") (pin "J2.2") (pinfunction "GND.2_J2.2") (pintype "power_in"))
      (node (ref "R.") (pin "1") (pinfunction "1_1") (pintype "passive"))
      (node (ref "R10") (pin "1") (pinfunction "1_1") (pintype "passive"))
      (node (ref "R100") (pin "1") (pinfunction "1_1") (pintype "passive"))
      (node (ref "R12") (pin "1") (pinfunction "1_1") (pintype "passive"))
      (node (ref "R14") (pin "1") (pinfunction "1_1") (pintype "passive"))
      (node (ref "R16") (pin "1") (pinfunction "1_1") (pintype "passive"))
      (node (ref "R18") (pin "1") (pinfunction "1_1") (pintype "passive"))
      (node (ref "R2") (pin "1") (pinfunction "1_1") (pintype "passive"))
      (node (ref "R20") (pin "1") (pinfunction "1_1") (pintype "passive"))
      (node (ref "R22") (pin "1") (pinfunction "1_1") (pintype "passive"))
      (node (ref "R24") (pin "1") (pinfunction "1_1") (pintype "passive"))
      (node (ref "R26") (pin "1") (pinfunction "1_1") (pintype "passive"))
      (node (ref "R28") (pin "1") (pinfunction "1_1") (pintype "passive"))
      (node (ref "R30") (pin "1") (pinfunction "1_1") (pintype "passive"))
      (node (ref "R32") (pin "1") (pinfunction "1_1") (pintype "passive"))
      (node (ref "R34") (pin "1") (pinfunction "1_1") (pintype "passive"))
      (node (ref "R36") (pin "1") (pinfunction "1_1") (pintype "passive"))
      (node (ref "R38") (pin "1") (pinfunction "1_1") (pintype "passive"))
      (node (ref "R4") (pin "1") (pinfunction "1_1") (pintype "passive"))
      (node (ref "R40") (pin "1") (pinfunction "1_1") (pintype "passive"))
      (node (ref "R42") (pin "1") (pinfunction "1_1") (pintype "passive"))
      (node (ref "R44") (pin "1") (pinfunction "1_1") (pintype "passive"))
      (node (ref "R46") (pin "1") (pinfunction "1_1") (pintype "passive"))
      (node (ref "R48") (pin "1") (pinfunction "1_1") (pintype "passive"))
      (node (ref "R50") (pin "1") (pinfunction "1_1") (pintype "passive"))
      (node (ref "R52") (pin "1") (pinfunction "1_1") (pintype "passive"))
      (node (ref "R54") (pin "1") (pinfunction "1_1") (pintype "passive"))
      (node (ref "R56") (pin "1") (pinfunction "1_1") (pintype "passive"))
      (node (ref "R58") (pin "1") (pinfunction "1_1") (pintype "passive"))
      (node (ref "R6") (pin "1") (pinfunction "1_1") (pintype "passive"))
      (node (ref "R60") (pin "1") (pinfunction "1_1") (pintype "passive"))
      (node (ref "R62") (pin "1") (pinfunction "1_1") (pintype "passive"))
      (node (ref "R64") (pin "1") (pinfunction "1_1") (pintype "passive"))
      (node (ref "R66") (pin "1") (pinfunction "1_1") (pintype "passive"))
      (node (ref "R68") (pin "1") (pinfunction "1_1") (pintype "passive"))
      (node (ref "R70") (pin "1") (pinfunction "1_1") (pintype "passive"))
      (node (ref "R72") (pin "1") (pinfunction "1_1") (pintype "passive"))
      (node (ref "R74") (pin "1") (pinfunction "1_1") (pintype "passive"))
      (node (ref "R76") (pin "1") (pinfunction "1_1") (pintype "passive"))
      (node (ref "R78") (pin "1") (pinfunction "1_1") (pintype "passive"))
      (node (ref "R8") (pin "1") (pinfunction "1_1") (pintype "passive"))
      (node (ref "R80") (pin "1") (pinfunction "1_1") (pintype "passive"))
      (node (ref "R82") (pin "1") (pinfunction "1_1") (pintype "passive"))
      (node (ref "R84") (pin "1") (pinfunction "1_1") (pintype "passive"))
      (node (ref "R86") (pin "1") (pinfunction "1_1") (pintype "passive"))
      (node (ref "R88") (pin "1") (pinfunction "1_1") (pintype "passive"))
      (node (ref "R90") (pin "1") (pinfunction "1_1") (pintype "passive"))
      (node (ref "R92") (pin "1") (pinfunction "1_1") (pintype "passive"))
      (node (ref "R94") (pin "1") (pinfunction "1_1") (pintype "passive"))
      (node (ref "R96") (pin "1") (pinfunction "1_1") (pintype "passive"))
      (node (ref "R98") (pin "1") (pinfunction "1_1") (pintype "passive"))
      (node (ref "U$1") (pin "J2.1") (pinfunction "GND_J2.1") (pintype "power_in"))
      (node (ref "U$2") (pin "J2.1") (pinfunction "GND_J2.1") (pintype "power_in"))
    )
    (net (code "14") (name "Net-(C2-Pad+)") (class "Default")
      (node (ref "C2") (pin "+") (pinfunction "+_+") (pintype "passive"))
      (node (ref "JP1") (pin "1") (pinfunction "1_1") (pintype "passive"))
    )
    (net (code "15") (name "Net-(C4-Pad+)") (class "Default")
      (node (ref "C4") (pin "+") (pinfunction "+_+") (pintype "passive"))
      (node (ref "D1") (pin "C") (pinfunction "C_C") (pintype "passive"))
      (node (ref "R") (pin "2") (pinfunction "2_2") (pintype "passive"))
      (node (ref "SW3") (pin "1") (pinfunction "1_1") (pintype "passive"))
    )
    (net (code "16") (name "Net-(D2-PadA)") (class "Default")
      (node (ref "D2") (pin "A") (pinfunction "A_A") (pintype "passive"))
      (node (ref "R1") (pin "2") (pinfunction "2_2") (pintype "passive"))
      (node (ref "SV1") (pin "1") (pinfunction "1_1") (pintype "passive"))
    )
    (net (code "17") (name "Net-(D3-PadA)") (class "Default")
      (node (ref "D3") (pin "A") (pinfunction "A_A") (pintype "passive"))
      (node (ref "R3") (pin "2") (pinfunction "2_2") (pintype "passive"))
      (node (ref "SV1") (pin "2") (pinfunction "2_2") (pintype "passive"))
    )
    (net (code "18") (name "Net-(D4-PadA)") (class "Default")
      (node (ref "D4") (pin "A") (pinfunction "A_A") (pintype "passive"))
      (node (ref "R5") (pin "2") (pinfunction "2_2") (pintype "passive"))
      (node (ref "SV1") (pin "3") (pinfunction "3_3") (pintype "passive"))
    )
    (net (code "19") (name "Net-(D5-PadA)") (class "Default")
      (node (ref "D5") (pin "A") (pinfunction "A_A") (pintype "passive"))
      (node (ref "R7") (pin "2") (pinfunction "2_2") (pintype "passive"))
      (node (ref "SV1") (pin "4") (pinfunction "4_4") (pintype "passive"))
    )
    (net (code "20") (name "Net-(D6-PadA)") (class "Default")
      (node (ref "D6") (pin "A") (pinfunction "A_A") (pintype "passive"))
      (node (ref "R9") (pin "2") (pinfunction "2_2") (pintype "passive"))
      (node (ref "SV1") (pin "5") (pinfunction "5_5") (pintype "passive"))
    )
    (net (code "21") (name "Net-(D7-PadA)") (class "Default")
      (node (ref "D7") (pin "A") (pinfunction "A_A") (pintype "passive"))
      (node (ref "R11") (pin "2") (pinfunction "2_2") (pintype "passive"))
      (node (ref "SV1") (pin "6") (pinfunction "6_6") (pintype "passive"))
    )
    (net (code "22") (name "Net-(D8-PadA)") (class "Default")
      (node (ref "D8") (pin "A") (pinfunction "A_A") (pintype "passive"))
      (node (ref "R13") (pin "2") (pinfunction "2_2") (pintype "passive"))
      (node (ref "SV1") (pin "7") (pinfunction "7_7") (pintype "passive"))
    )
    (net (code "23") (name "Net-(D9-PadA)") (class "Default")
      (node (ref "D9") (pin "A") (pinfunction "A_A") (pintype "passive"))
      (node (ref "R15") (pin "2") (pinfunction "2_2") (pintype "passive"))
      (node (ref "SV1") (pin "8") (pinfunction "8_8") (pintype "passive"))
    )
    (net (code "24") (name "Net-(D10-PadA)") (class "Default")
      (node (ref "D10") (pin "A") (pinfunction "A_A") (pintype "passive"))
      (node (ref "R17") (pin "2") (pinfunction "2_2") (pintype "passive"))
      (node (ref "SV1") (pin "9") (pinfunction "9_9") (pintype "passive"))
    )
    (net (code "25") (name "Net-(D11-PadA)") (class "Default")
      (node (ref "D11") (pin "A") (pinfunction "A_A") (pintype "passive"))
      (node (ref "R19") (pin "2") (pinfunction "2_2") (pintype "passive"))
      (node (ref "SV1") (pin "10") (pinfunction "10_10") (pintype "passive"))
    )
    (net (code "26") (name "Net-(D12-PadA)") (class "Default")
      (node (ref "D12") (pin "A") (pinfunction "A_A") (pintype "passive"))
      (node (ref "R21") (pin "2") (pinfunction "2_2") (pintype "passive"))
      (node (ref "SV2") (pin "1") (pinfunction "1_1") (pintype "passive"))
    )
    (net (code "27") (name "Net-(D13-PadA)") (class "Default")
      (node (ref "D13") (pin "A") (pinfunction "A_A") (pintype "passive"))
      (node (ref "R23") (pin "2") (pinfunction "2_2") (pintype "passive"))
      (node (ref "SV2") (pin "2") (pinfunction "2_2") (pintype "passive"))
    )
    (net (code "28") (name "Net-(D14-PadA)") (class "Default")
      (node (ref "D14") (pin "A") (pinfunction "A_A") (pintype "passive"))
      (node (ref "R25") (pin "2") (pinfunction "2_2") (pintype "passive"))
      (node (ref "SV2") (pin "3") (pinfunction "3_3") (pintype "passive"))
    )
    (net (code "29") (name "Net-(D15-PadA)") (class "Default")
      (node (ref "D15") (pin "A") (pinfunction "A_A") (pintype "passive"))
      (node (ref "R27") (pin "2") (pinfunction "2_2") (pintype "passive"))
      (node (ref "SV2") (pin "4") (pinfunction "4_4") (pintype "passive"))
    )
    (net (code "30") (name "Net-(D16-PadA)") (class "Default")
      (node (ref "D16") (pin "A") (pinfunction "A_A") (pintype "passive"))
      (node (ref "R29") (pin "2") (pinfunction "2_2") (pintype "passive"))
      (node (ref "SV2") (pin "5") (pinfunction "5_5") (pintype "passive"))
    )
    (net (code "31") (name "Net-(D17-PadA)") (class "Default")
      (node (ref "D17") (pin "A") (pinfunction "A_A") (pintype "passive"))
      (node (ref "R31") (pin "2") (pinfunction "2_2") (pintype "passive"))
      (node (ref "SV2") (pin "6") (pinfunction "6_6") (pintype "passive"))
    )
    (net (code "32") (name "Net-(D18-PadA)") (class "Default")
      (node (ref "D18") (pin "A") (pinfunction "A_A") (pintype "passive"))
      (node (ref "R33") (pin "2") (pinfunction "2_2") (pintype "passive"))
      (node (ref "SV2") (pin "7") (pinfunction "7_7") (pintype "passive"))
    )
    (net (code "33") (name "Net-(D19-PadA)") (class "Default")
      (node (ref "D19") (pin "A") (pinfunction "A_A") (pintype "passive"))
      (node (ref "R35") (pin "2") (pinfunction "2_2") (pintype "passive"))
      (node (ref "SV2") (pin "8") (pinfunction "8_8") (pintype "passive"))
    )
    (net (code "34") (name "Net-(D20-PadA)") (class "Default")
      (node (ref "D20") (pin "A") (pinfunction "A_A") (pintype "passive"))
      (node (ref "R37") (pin "2") (pinfunction "2_2") (pintype "passive"))
      (node (ref "SV2") (pin "9") (pinfunction "9_9") (pintype "passive"))
    )
    (net (code "35") (name "Net-(D21-PadA)") (class "Default")
      (node (ref "D21") (pin "A") (pinfunction "A_A") (pintype "passive"))
      (node (ref "R39") (pin "2") (pinfunction "2_2") (pintype "passive"))
      (node (ref "SV2") (pin "10") (pinfunction "10_10") (pintype "passive"))
    )
    (net (code "36") (name "Net-(D22-PadA)") (class "Default")
      (node (ref "D22") (pin "A") (pinfunction "A_A") (pintype "passive"))
      (node (ref "R41") (pin "2") (pinfunction "2_2") (pintype "passive"))
      (node (ref "SV3") (pin "1") (pinfunction "1_1") (pintype "passive"))
    )
    (net (code "37") (name "Net-(D23-PadA)") (class "Default")
      (node (ref "D23") (pin "A") (pinfunction "A_A") (pintype "passive"))
      (node (ref "R43") (pin "2") (pinfunction "2_2") (pintype "passive"))
      (node (ref "SV3") (pin "2") (pinfunction "2_2") (pintype "passive"))
    )
    (net (code "38") (name "Net-(D24-PadA)") (class "Default")
      (node (ref "D24") (pin "A") (pinfunction "A_A") (pintype "passive"))
      (node (ref "R45") (pin "2") (pinfunction "2_2") (pintype "passive"))
      (node (ref "SV3") (pin "3") (pinfunction "3_3") (pintype "passive"))
    )
    (net (code "39") (name "Net-(D25-PadA)") (class "Default")
      (node (ref "D25") (pin "A") (pinfunction "A_A") (pintype "passive"))
      (node (ref "R47") (pin "2") (pinfunction "2_2") (pintype "passive"))
      (node (ref "SV3") (pin "4") (pinfunction "4_4") (pintype "passive"))
    )
    (net (code "40") (name "Net-(D26-PadA)") (class "Default")
      (node (ref "D26") (pin "A") (pinfunction "A_A") (pintype "passive"))
      (node (ref "R49") (pin "2") (pinfunction "2_2") (pintype "passive"))
      (node (ref "SV3") (pin "5") (pinfunction "5_5") (pintype "passive"))
    )
    (net (code "41") (name "Net-(D27-PadA)") (class "Default")
      (node (ref "D27") (pin "A") (pinfunction "A_A") (pintype "passive"))
      (node (ref "R51") (pin "2") (pinfunction "2_2") (pintype "passive"))
      (node (ref "SV3") (pin "6") (pinfunction "6_6") (pintype "passive"))
    )
    (net (code "42") (name "Net-(D28-PadA)") (class "Default")
      (node (ref "D28") (pin "A") (pinfunction "A_A") (pintype "passive"))
      (node (ref "R53") (pin "2") (pinfunction "2_2") (pintype "passive"))
      (node (ref "SV3") (pin "7") (pinfunction "7_7") (pintype "passive"))
    )
    (net (code "43") (name "Net-(D29-PadA)") (class "Default")
      (node (ref "D29") (pin "A") (pinfunction "A_A") (pintype "passive"))
      (node (ref "R55") (pin "2") (pinfunction "2_2") (pintype "passive"))
      (node (ref "SV3") (pin "8") (pinfunction "8_8") (pintype "passive"))
    )
    (net (code "44") (name "Net-(D30-PadA)") (class "Default")
      (node (ref "D30") (pin "A") (pinfunction "A_A") (pintype "passive"))
      (node (ref "R57") (pin "2") (pinfunction "2_2") (pintype "passive"))
      (node (ref "SV3") (pin "9") (pinfunction "9_9") (pintype "passive"))
    )
    (net (code "45") (name "Net-(D31-PadA)") (class "Default")
      (node (ref "D31") (pin "A") (pinfunction "A_A") (pintype "passive"))
      (node (ref "R59") (pin "2") (pinfunction "2_2") (pintype "passive"))
      (node (ref "SV3") (pin "10") (pinfunction "10_10") (pintype "passive"))
    )
    (net (code "46") (name "Net-(D32-PadA)") (class "Default")
      (node (ref "D32") (pin "A") (pinfunction "A_A") (pintype "passive"))
      (node (ref "R61") (pin "2") (pinfunction "2_2") (pintype "passive"))
      (node (ref "SV4") (pin "1") (pinfunction "1_1") (pintype "passive"))
    )
    (net (code "47") (name "Net-(D33-PadA)") (class "Default")
      (node (ref "D33") (pin "A") (pinfunction "A_A") (pintype "passive"))
      (node (ref "R63") (pin "2") (pinfunction "2_2") (pintype "passive"))
      (node (ref "SV4") (pin "2") (pinfunction "2_2") (pintype "passive"))
    )
    (net (code "48") (name "Net-(D34-PadA)") (class "Default")
      (node (ref "D34") (pin "A") (pinfunction "A_A") (pintype "passive"))
      (node (ref "R65") (pin "2") (pinfunction "2_2") (pintype "passive"))
      (node (ref "SV4") (pin "3") (pinfunction "3_3") (pintype "passive"))
    )
    (net (code "49") (name "Net-(D35-PadA)") (class "Default")
      (node (ref "D35") (pin "A") (pinfunction "A_A") (pintype "passive"))
      (node (ref "R67") (pin "2") (pinfunction "2_2") (pintype "passive"))
      (node (ref "SV4") (pin "4") (pinfunction "4_4") (pintype "passive"))
    )
    (net (code "50") (name "Net-(D36-PadA)") (class "Default")
      (node (ref "D36") (pin "A") (pinfunction "A_A") (pintype "passive"))
      (node (ref "R69") (pin "2") (pinfunction "2_2") (pintype "passive"))
      (node (ref "SV4") (pin "5") (pinfunction "5_5") (pintype "passive"))
    )
    (net (code "51") (name "Net-(D37-PadA)") (class "Default")
      (node (ref "D37") (pin "A") (pinfunction "A_A") (pintype "passive"))
      (node (ref "R71") (pin "2") (pinfunction "2_2") (pintype "passive"))
      (node (ref "SV4") (pin "6") (pinfunction "6_6") (pintype "passive"))
    )
    (net (code "52") (name "Net-(D38-PadA)") (class "Default")
      (node (ref "D38") (pin "A") (pinfunction "A_A") (pintype "passive"))
      (node (ref "R73") (pin "2") (pinfunction "2_2") (pintype "passive"))
      (node (ref "SV5") (pin "1") (pinfunction "1_1") (pintype "passive"))
    )
    (net (code "53") (name "Net-(D39-PadA)") (class "Default")
      (node (ref "D39") (pin "A") (pinfunction "A_A") (pintype "passive"))
      (node (ref "R75") (pin "2") (pinfunction "2_2") (pintype "passive"))
      (node (ref "SV5") (pin "2") (pinfunction "2_2") (pintype "passive"))
    )
    (net (code "54") (name "Net-(D40-PadA)") (class "Default")
      (node (ref "D40") (pin "A") (pinfunction "A_A") (pintype "passive"))
      (node (ref "R77") (pin "2") (pinfunction "2_2") (pintype "passive"))
      (node (ref "SV5") (pin "3") (pinfunction "3_3") (pintype "passive"))
    )
    (net (code "55") (name "Net-(D41-PadA)") (class "Default")
      (node (ref "D41") (pin "A") (pinfunction "A_A") (pintype "passive"))
      (node (ref "R79") (pin "2") (pinfunction "2_2") (pintype "passive"))
      (node (ref "SV5") (pin "4") (pinfunction "4_4") (pintype "passive"))
    )
    (net (code "56") (name "Net-(D42-PadA)") (class "Default")
      (node (ref "D42") (pin "A") (pinfunction "A_A") (pintype "passive"))
      (node (ref "R81") (pin "2") (pinfunction "2_2") (pintype "passive"))
      (node (ref "SV5") (pin "5") (pinfunction "5_5") (pintype "passive"))
    )
    (net (code "57") (name "Net-(D43-PadA)") (class "Default")
      (node (ref "D43") (pin "A") (pinfunction "A_A") (pintype "passive"))
      (node (ref "R83") (pin "2") (pinfunction "2_2") (pintype "passive"))
      (node (ref "SV5") (pin "6") (pinfunction "6_6") (pintype "passive"))
    )
    (net (code "58") (name "Net-(D44-PadA)") (class "Default")
      (node (ref "D44") (pin "A") (pinfunction "A_A") (pintype "passive"))
      (node (ref "R85") (pin "2") (pinfunction "2_2") (pintype "passive"))
      (node (ref "SV6") (pin "1") (pinfunction "1_1") (pintype "passive"))
    )
    (net (code "59") (name "Net-(D45-PadA)") (class "Default")
      (node (ref "D45") (pin "A") (pinfunction "A_A") (pintype "passive"))
      (node (ref "R87") (pin "2") (pinfunction "2_2") (pintype "passive"))
      (node (ref "SV6") (pin "2") (pinfunction "2_2") (pintype "passive"))
    )
    (net (code "60") (name "Net-(D46-PadA)") (class "Default")
      (node (ref "D46") (pin "A") (pinfunction "A_A") (pintype "passive"))
      (node (ref "R89") (pin "2") (pinfunction "2_2") (pintype "passive"))
      (node (ref "SV6") (pin "3") (pinfunction "3_3") (pintype "passive"))
    )
    (net (code "61") (name "Net-(D47-PadA)") (class "Default")
      (node (ref "D47") (pin "A") (pinfunction "A_A") (pintype "passive"))
      (node (ref "R91") (pin "2") (pinfunction "2_2") (pintype "passive"))
      (node (ref "SV6") (pin "4") (pinfunction "4_4") (pintype "passive"))
    )
    (net (code "62") (name "Net-(D48-PadA)") (class "Default")
      (node (ref "D48") (pin "A") (pinfunction "A_A") (pintype "passive"))
      (node (ref "R93") (pin "2") (pinfunction "2_2") (pintype "passive"))
      (node (ref "SV6") (pin "5") (pinfunction "5_5") (pintype "passive"))
    )
    (net (code "63") (name "Net-(D49-PadA)") (class "Default")
      (node (ref "D49") (pin "A") (pinfunction "A_A") (pintype "passive"))
      (node (ref "R95") (pin "2") (pinfunction "2_2") (pintype "passive"))
      (node (ref "SV6") (pin "6") (pinfunction "6_6") (pintype "passive"))
    )
    (net (code "64") (name "Net-(D50-PadC)") (class "Default")
      (node (ref "D50") (pin "C") (pinfunction "C_C") (pintype "passive"))
      (node (ref "GND_NURSECALL") (pin "1") (pinfunction "1_1") (pintype "passive"))
    )
    (net (code "65") (name "Net-(INDIKATOR_ON-PadA)") (class "Default")
      (node (ref "INDIKATOR_ON") (pin "A") (pinfunction "A_A") (pintype "passive"))
      (node (ref "R") (pin "1") (pinfunction "1_1") (pintype "passive"))
    )
    (net (code "66") (name "Net-(LED_TX-Pad2)") (class "Default")
      (node (ref "LED_TX") (pin "2") (pinfunction "2_2") (pintype "passive"))
      (node (ref "R.") (pin "2") (pinfunction "2_2") (pintype "passive"))
    )
    (net (code "67") (name "Net-(M2-D1{slash}TX)") (class "Default")
      (node (ref "LED_TX") (pin "1") (pinfunction "1_1") (pintype "passive"))
      (node (ref "M2") (pin "J1.1") (pinfunction "D1/TX_J1.1") (pintype "bidirectional"))
    )
    (net (code "68") (name "Net-(M2-D3)") (class "Default")
      (node (ref "D52") (pin "C") (pinfunction "C_C") (pintype "passive"))
      (node (ref "M2") (pin "J1.6") (pinfunction "D3_J1.6") (pintype "bidirectional"))
      (node (ref "R97") (pin "1") (pinfunction "1_1") (pintype "passive"))
      (node (ref "R98") (pin "2") (pinfunction "2_2") (pintype "passive"))
    )
    (net (code "69") (name "Net-(M2-GND.1)") (class "Default")
      (node (ref "C2") (pin "-") (pinfunction "-_-") (pintype "passive"))
      (node (ref "C6") (pin "2") (pinfunction "2_2") (pintype "passive"))
      (node (ref "D52") (pin "A") (pinfunction "A_A") (pintype "passive"))
      (node (ref "M2") (pin "J1.4") (pinfunction "GND.1_J1.4") (pintype "power_in"))
      (node (ref "U$3") (pin "J2.1") (pinfunction "GND_J2.1") (pintype "power_in"))
    )
    (net (code "70") (name "Net-(M2-RST.1)") (class "Default")
      (node (ref "JP1") (pin "2") (pinfunction "2_2") (pintype "passive"))
      (node (ref "M2") (pin "J1.3") (pinfunction "RST.1_J1.3") (pintype "bidirectional"))
    )
    (net (code "71") (name "Net-(M2-VIN)") (class "Default")
      (node (ref "M2") (pin "J2.1") (pinfunction "VIN_J2.1") (pintype "power_in"))
      (node (ref "SW3") (pin "2") (pinfunction "2_2") (pintype "passive"))
    )
    (net (code "72") (name "Net-(U$1-C0)") (class "Default")
      (node (ref "R1") (pin "1") (pinfunction "1_1") (pintype "passive"))
      (node (ref "R2") (pin "2") (pinfunction "2_2") (pintype "passive"))
      (node (ref "U$1") (pin "J1.1") (pinfunction "C0_J1.1") (pintype "bidirectional"))
    )
    (net (code "73") (name "Net-(U$1-C1)") (class "Default")
      (node (ref "R3") (pin "1") (pinfunction "1_1") (pintype "passive"))
      (node (ref "R4") (pin "2") (pinfunction "2_2") (pintype "passive"))
      (node (ref "U$1") (pin "J1.2") (pinfunction "C1_J1.2") (pintype "bidirectional"))
    )
    (net (code "74") (name "Net-(U$1-C2)") (class "Default")
      (node (ref "R5") (pin "1") (pinfunction "1_1") (pintype "passive"))
      (node (ref "R6") (pin "2") (pinfunction "2_2") (pintype "passive"))
      (node (ref "U$1") (pin "J1.3") (pinfunction "C2_J1.3") (pintype "bidirectional"))
    )
    (net (code "75") (name "Net-(U$1-C3)") (class "Default")
      (node (ref "R7") (pin "1") (pinfunction "1_1") (pintype "passive"))
      (node (ref "R8") (pin "2") (pinfunction "2_2") (pintype "passive"))
      (node (ref "U$1") (pin "J1.4") (pinfunction "C3_J1.4") (pintype "bidirectional"))
    )
    (net (code "76") (name "Net-(U$1-C4)") (class "Default")
      (node (ref "R10") (pin "2") (pinfunction "2_2") (pintype "passive"))
      (node (ref "R9") (pin "1") (pinfunction "1_1") (pintype "passive"))
      (node (ref "U$1") (pin "J1.5") (pinfunction "C4_J1.5") (pintype "bidirectional"))
    )
    (net (code "77") (name "Net-(U$1-C5)") (class "Default")
      (node (ref "R11") (pin "1") (pinfunction "1_1") (pintype "passive"))
      (node (ref "R12") (pin "2") (pinfunction "2_2") (pintype "passive"))
      (node (ref "U$1") (pin "J1.6") (pinfunction "C5_J1.6") (pintype "bidirectional"))
    )
    (net (code "78") (name "Net-(U$1-C6)") (class "Default")
      (node (ref "R13") (pin "1") (pinfunction "1_1") (pintype "passive"))
      (node (ref "R14") (pin "2") (pinfunction "2_2") (pintype "passive"))
      (node (ref "U$1") (pin "J1.7") (pinfunction "C6_J1.7") (pintype "bidirectional"))
    )
    (net (code "79") (name "Net-(U$1-C7)") (class "Default")
      (node (ref "R15") (pin "1") (pinfunction "1_1") (pintype "passive"))
      (node (ref "R16") (pin "2") (pinfunction "2_2") (pintype "passive"))
      (node (ref "U$1") (pin "J1.8") (pinfunction "C7_J1.8") (pintype "bidirectional"))
    )
    (net (code "80") (name "Net-(U$1-C8)") (class "Default")
      (node (ref "R17") (pin "1") (pinfunction "1_1") (pintype "passive"))
      (node (ref "R18") (pin "2") (pinfunction "2_2") (pintype "passive"))
      (node (ref "U$1") (pin "J1.9") (pinfunction "C8_J1.9") (pintype "bidirectional"))
    )
    (net (code "81") (name "Net-(U$1-C9)") (class "Default")
      (node (ref "R19") (pin "1") (pinfunction "1_1") (pintype "passive"))
      (node (ref "R20") (pin "2") (pinfunction "2_2") (pintype "passive"))
      (node (ref "U$1") (pin "J1.10") (pinfunction "C9_J1.10") (pintype "bidirectional"))
    )
    (net (code "82") (name "Net-(U$1-C10)") (class "Default")
      (node (ref "R21") (pin "1") (pinfunction "1_1") (pintype "passive"))
      (node (ref "R22") (pin "2") (pinfunction "2_2") (pintype "passive"))
      (node (ref "U$1") (pin "J1.11") (pinfunction "C10_J1.11") (pintype "bidirectional"))
    )
    (net (code "83") (name "Net-(U$1-C11)") (class "Default")
      (node (ref "R23") (pin "1") (pinfunction "1_1") (pintype "passive"))
      (node (ref "R24") (pin "2") (pinfunction "2_2") (pintype "passive"))
      (node (ref "U$1") (pin "J1.12") (pinfunction "C11_J1.12") (pintype "bidirectional"))
    )
    (net (code "84") (name "Net-(U$1-C12)") (class "Default")
      (node (ref "R25") (pin "1") (pinfunction "1_1") (pintype "passive"))
      (node (ref "R26") (pin "2") (pinfunction "2_2") (pintype "passive"))
      (node (ref "U$1") (pin "J1.13") (pinfunction "C12_J1.13") (pintype "bidirectional"))
    )
    (net (code "85") (name "Net-(U$1-C13)") (class "Default")
      (node (ref "R27") (pin "1") (pinfunction "1_1") (pintype "passive"))
      (node (ref "R28") (pin "2") (pinfunction "2_2") (pintype "passive"))
      (node (ref "U$1") (pin "J1.14") (pinfunction "C13_J1.14") (pintype "bidirectional"))
    )
    (net (code "86") (name "Net-(U$1-C14)") (class "Default")
      (node (ref "R29") (pin "1") (pinfunction "1_1") (pintype "passive"))
      (node (ref "R30") (pin "2") (pinfunction "2_2") (pintype "passive"))
      (node (ref "U$1") (pin "J1.15") (pinfunction "C14_J1.15") (pintype "bidirectional"))
    )
    (net (code "87") (name "Net-(U$1-C15)") (class "Default")
      (node (ref "R31") (pin "1") (pinfunction "1_1") (pintype "passive"))
      (node (ref "R32") (pin "2") (pinfunction "2_2") (pintype "passive"))
      (node (ref "U$1") (pin "J1.16") (pinfunction "C15_J1.16") (pintype "bidirectional"))
    )
    (net (code "88") (name "Net-(U$1-EN)") (class "Default")
      (node (ref "C1") (pin "1") (pinfunction "1_1") (pintype "passive"))
      (node (ref "U$1") (pin "J2.3") (pinfunction "EN_J2.3") (pintype "input"))
    )
    (net (code "89") (name "Net-(U$2-C0)") (class "Default")
      (node (ref "R33") (pin "1") (pinfunction "1_1") (pintype "passive"))
      (node (ref "R34") (pin "2") (pinfunction "2_2") (pintype "passive"))
      (node (ref "U$2") (pin "J1.1") (pinfunction "C0_J1.1") (pintype "bidirectional"))
    )
    (net (code "90") (name "Net-(U$2-C1)") (class "Default")
      (node (ref "R35") (pin "1") (pinfunction "1_1") (pintype "passive"))
      (node (ref "R36") (pin "2") (pinfunction "2_2") (pintype "passive"))
      (node (ref "U$2") (pin "J1.2") (pinfunction "C1_J1.2") (pintype "bidirectional"))
    )
    (net (code "91") (name "Net-(U$2-C2)") (class "Default")
      (node (ref "R37") (pin "1") (pinfunction "1_1") (pintype "passive"))
      (node (ref "R38") (pin "2") (pinfunction "2_2") (pintype "passive"))
      (node (ref "U$2") (pin "J1.3") (pinfunction "C2_J1.3") (pintype "bidirectional"))
    )
    (net (code "92") (name "Net-(U$2-C3)") (class "Default")
      (node (ref "R39") (pin "1") (pinfunction "1_1") (pintype "passive"))
      (node (ref "R40") (pin "2") (pinfunction "2_2") (pintype "passive"))
      (node (ref "U$2") (pin "J1.4") (pinfunction "C3_J1.4") (pintype "bidirectional"))
    )
    (net (code "93") (name "Net-(U$2-C4)") (class "Default")
      (node (ref "R41") (pin "1") (pinfunction "1_1") (pintype "passive"))
      (node (ref "R42") (pin "2") (pinfunction "2_2") (pintype "passive"))
      (node (ref "U$2") (pin "J1.5") (pinfunction "C4_J1.5") (pintype "bidirectional"))
    )
    (net (code "94") (name "Net-(U$2-C5)") (class "Default")
      (node (ref "R43") (pin "1") (pinfunction "1_1") (pintype "passive"))
      (node (ref "R44") (pin "2") (pinfunction "2_2") (pintype "passive"))
      (node (ref "U$2") (pin "J1.6") (pinfunction "C5_J1.6") (pintype "bidirectional"))
    )
    (net (code "95") (name "Net-(U$2-C6)") (class "Default")
      (node (ref "R45") (pin "1") (pinfunction "1_1") (pintype "passive"))
      (node (ref "R46") (pin "2") (pinfunction "2_2") (pintype "passive"))
      (node (ref "U$2") (pin "J1.7") (pinfunction "C6_J1.7") (pintype "bidirectional"))
    )
    (net (code "96") (name "Net-(U$2-C7)") (class "Default")
      (node (ref "R47") (pin "1") (pinfunction "1_1") (pintype "passive"))
      (node (ref "R48") (pin "2") (pinfunction "2_2") (pintype "passive"))
      (node (ref "U$2") (pin "J1.8") (pinfunction "C7_J1.8") (pintype "bidirectional"))
    )
    (net (code "97") (name "Net-(U$2-C8)") (class "Default")
      (node (ref "R49") (pin "1") (pinfunction "1_1") (pintype "passive"))
      (node (ref "R50") (pin "2") (pinfunction "2_2") (pintype "passive"))
      (node (ref "U$2") (pin "J1.9") (pinfunction "C8_J1.9") (pintype "bidirectional"))
    )
    (net (code "98") (name "Net-(U$2-C9)") (class "Default")
      (node (ref "R51") (pin "1") (pinfunction "1_1") (pintype "passive"))
      (node (ref "R52") (pin "2") (pinfunction "2_2") (pintype "passive"))
      (node (ref "U$2") (pin "J1.10") (pinfunction "C9_J1.10") (pintype "bidirectional"))
    )
    (net (code "99") (name "Net-(U$2-C10)") (class "Default")
      (node (ref "R53") (pin "1") (pinfunction "1_1") (pintype "passive"))
      (node (ref "R54") (pin "2") (pinfunction "2_2") (pintype "passive"))
      (node (ref "U$2") (pin "J1.11") (pinfunction "C10_J1.11") (pintype "bidirectional"))
    )
    (net (code "100") (name "Net-(U$2-C11)") (class "Default")
      (node (ref "R55") (pin "1") (pinfunction "1_1") (pintype "passive"))
      (node (ref "R56") (pin "2") (pinfunction "2_2") (pintype "passive"))
      (node (ref "U$2") (pin "J1.12") (pinfunction "C11_J1.12") (pintype "bidirectional"))
    )
    (net (code "101") (name "Net-(U$2-C12)") (class "Default")
      (node (ref "R57") (pin "1") (pinfunction "1_1") (pintype "passive"))
      (node (ref "R58") (pin "2") (pinfunction "2_2") (pintype "passive"))
      (node (ref "U$2") (pin "J1.13") (pinfunction "C12_J1.13") (pintype "bidirectional"))
    )
    (net (code "102") (name "Net-(U$2-C13)") (class "Default")
      (node (ref "R59") (pin "1") (pinfunction "1_1") (pintype "passive"))
      (node (ref "R60") (pin "2") (pinfunction "2_2") (pintype "passive"))
      (node (ref "U$2") (pin "J1.14") (pinfunction "C13_J1.14") (pintype "bidirectional"))
    )
    (net (code "103") (name "Net-(U$2-C14)") (class "Default")
      (node (ref "R61") (pin "1") (pinfunction "1_1") (pintype "passive"))
      (node (ref "R62") (pin "2") (pinfunction "2_2") (pintype "passive"))
      (node (ref "U$2") (pin "J1.15") (pinfunction "C14_J1.15") (pintype "bidirectional"))
    )
    (net (code "104") (name "Net-(U$2-C15)") (class "Default")
      (node (ref "R63") (pin "1") (pinfunction "1_1") (pintype "passive"))
      (node (ref "R64") (pin "2") (pinfunction "2_2") (pintype "passive"))
      (node (ref "U$2") (pin "J1.16") (pinfunction "C15_J1.16") (pintype "bidirectional"))
    )
    (net (code "105") (name "Net-(U$2-EN)") (class "Default")
      (node (ref "C5") (pin "1") (pinfunction "1_1") (pintype "passive"))
      (node (ref "U$2") (pin "J2.3") (pinfunction "EN_J2.3") (pintype "input"))
    )
    (net (code "106") (name "Net-(U$3-C0)") (class "Default")
      (node (ref "R65") (pin "1") (pinfunction "1_1") (pintype "passive"))
      (node (ref "R66") (pin "2") (pinfunction "2_2") (pintype "passive"))
      (node (ref "U$3") (pin "J1.1") (pinfunction "C0_J1.1") (pintype "bidirectional"))
    )
    (net (code "107") (name "Net-(U$3-C1)") (class "Default")
      (node (ref "R67") (pin "1") (pinfunction "1_1") (pintype "passive"))
      (node (ref "R68") (pin "2") (pinfunction "2_2") (pintype "passive"))
      (node (ref "U$3") (pin "J1.2") (pinfunction "C1_J1.2") (pintype "bidirectional"))
    )
    (net (code "108") (name "Net-(U$3-C2)") (class "Default")
      (node (ref "R69") (pin "1") (pinfunction "1_1") (pintype "passive"))
      (node (ref "R70") (pin "2") (pinfunction "2_2") (pintype "passive"))
      (node (ref "U$3") (pin "J1.3") (pinfunction "C2_J1.3") (pintype "bidirectional"))
    )
    (net (code "109") (name "Net-(U$3-C3)") (class "Default")
      (node (ref "R71") (pin "1") (pinfunction "1_1") (pintype "passive"))
      (node (ref "R72") (pin "2") (pinfunction "2_2") (pintype "passive"))
      (node (ref "U$3") (pin "J1.4") (pinfunction "C3_J1.4") (pintype "bidirectional"))
    )
    (net (code "110") (name "Net-(U$3-C4)") (class "Default")
      (node (ref "R73") (pin "1") (pinfunction "1_1") (pintype "passive"))
      (node (ref "R74") (pin "2") (pinfunction "2_2") (pintype "passive"))
      (node (ref "U$3") (pin "J1.5") (pinfunction "C4_J1.5") (pintype "bidirectional"))
    )
    (net (code "111") (name "Net-(U$3-C5)") (class "Default")
      (node (ref "R75") (pin "1") (pinfunction "1_1") (pintype "passive"))
      (node (ref "R76") (pin "2") (pinfunction "2_2") (pintype "passive"))
      (node (ref "U$3") (pin "J1.6") (pinfunction "C5_J1.6") (pintype "bidirectional"))
    )
    (net (code "112") (name "Net-(U$3-C6)") (class "Default")
      (node (ref "R77") (pin "1") (pinfunction "1_1") (pintype "passive"))
      (node (ref "R78") (pin "2") (pinfunction "2_2") (pintype "passive"))
      (node (ref "U$3") (pin "J1.7") (pinfunction "C6_J1.7") (pintype "bidirectional"))
    )
    (net (code "113") (name "Net-(U$3-C7)") (class "Default")
      (node (ref "R79") (pin "1") (pinfunction "1_1") (pintype "passive"))
      (node (ref "R80") (pin "2") (pinfunction "2_2") (pintype "passive"))
      (node (ref "U$3") (pin "J1.8") (pinfunction "C7_J1.8") (pintype "bidirectional"))
    )
    (net (code "114") (name "Net-(U$3-C8)") (class "Default")
      (node (ref "R81") (pin "1") (pinfunction "1_1") (pintype "passive"))
      (node (ref "R82") (pin "2") (pinfunction "2_2") (pintype "passive"))
      (node (ref "U$3") (pin "J1.9") (pinfunction "C8_J1.9") (pintype "bidirectional"))
    )
    (net (code "115") (name "Net-(U$3-C9)") (class "Default")
      (node (ref "R83") (pin "1") (pinfunction "1_1") (pintype "passive"))
      (node (ref "R84") (pin "2") (pinfunction "2_2") (pintype "passive"))
      (node (ref "U$3") (pin "J1.10") (pinfunction "C9_J1.10") (pintype "bidirectional"))
    )
    (net (code "116") (name "Net-(U$3-C10)") (class "Default")
      (node (ref "R85") (pin "1") (pinfunction "1_1") (pintype "passive"))
      (node (ref "R86") (pin "2") (pinfunction "2_2") (pintype "passive"))
      (node (ref "U$3") (pin "J1.11") (pinfunction "C10_J1.11") (pintype "bidirectional"))
    )
    (net (code "117") (name "Net-(U$3-C11)") (class "Default")
      (node (ref "R87") (pin "1") (pinfunction "1_1") (pintype "passive"))
      (node (ref "R88") (pin "2") (pinfunction "2_2") (pintype "passive"))
      (node (ref "U$3") (pin "J1.12") (pinfunction "C11_J1.12") (pintype "bidirectional"))
    )
    (net (code "118") (name "Net-(U$3-C12)") (class "Default")
      (node (ref "R89") (pin "1") (pinfunction "1_1") (pintype "passive"))
      (node (ref "R90") (pin "2") (pinfunction "2_2") (pintype "passive"))
      (node (ref "U$3") (pin "J1.13") (pinfunction "C12_J1.13") (pintype "bidirectional"))
    )
    (net (code "119") (name "Net-(U$3-C13)") (class "Default")
      (node (ref "R91") (pin "1") (pinfunction "1_1") (pintype "passive"))
      (node (ref "R92") (pin "2") (pinfunction "2_2") (pintype "passive"))
      (node (ref "U$3") (pin "J1.14") (pinfunction "C13_J1.14") (pintype "bidirectional"))
    )
    (net (code "120") (name "Net-(U$3-C14)") (class "Default")
      (node (ref "R93") (pin "1") (pinfunction "1_1") (pintype "passive"))
      (node (ref "R94") (pin "2") (pinfunction "2_2") (pintype "passive"))
      (node (ref "U$3") (pin "J1.15") (pinfunction "C14_J1.15") (pintype "bidirectional"))
    )
    (net (code "121") (name "Net-(U$3-C15)") (class "Default")
      (node (ref "R95") (pin "1") (pinfunction "1_1") (pintype "passive"))
      (node (ref "R96") (pin "2") (pinfunction "2_2") (pintype "passive"))
      (node (ref "U$3") (pin "J1.16") (pinfunction "C15_J1.16") (pintype "bidirectional"))
    )
    (net (code "122") (name "Net-(U$3-EN)") (class "Default")
      (node (ref "C6") (pin "1") (pinfunction "1_1") (pintype "passive"))
      (node (ref "U$3") (pin "J2.3") (pinfunction "EN_J2.3") (pintype "input"))
    )
    (net (code "123") (name "unconnected-(M2-A3-PadJ2.9)") (class "Default")
      (node (ref "M2") (pin "J2.9") (pinfunction "A3_J2.9") (pintype "bidirectional"))
    )
    (net (code "124") (name "unconnected-(M2-A4-PadJ2.8)") (class "Default")
      (node (ref "M2") (pin "J2.8") (pinfunction "A4_J2.8") (pintype "bidirectional"))
    )
    (net (code "125") (name "unconnected-(M2-A5-PadJ2.7)") (class "Default")
      (node (ref "M2") (pin "J2.7") (pinfunction "A5_J2.7") (pintype "bidirectional"))
    )
    (net (code "126") (name "unconnected-(M2-A6-PadJ2.6)") (class "Default")
      (node (ref "M2") (pin "J2.6") (pinfunction "A6_J2.6") (pintype "bidirectional"))
    )
    (net (code "127") (name "unconnected-(M2-A7-PadJ2.5)") (class "Default")
      (node (ref "M2") (pin "J2.5") (pinfunction "A7_J2.5") (pintype "bidirectional"))
    )
    (net (code "128") (name "unconnected-(M2-AREF-PadJ2.13)") (class "Default")
      (node (ref "M2") (pin "J2.13") (pinfunction "AREF_J2.13") (pintype "bidirectional"))
    )
    (net (code "129") (name "unconnected-(M2-D0{slash}RX-PadJ1.2)") (class "Default")
      (node (ref "M2") (pin "J1.2") (pinfunction "D0/RX_J1.2") (pintype "bidirectional"))
    )
    (net (code "130") (name "unconnected-(M2-D8-PadJ1.11)") (class "Default")
      (node (ref "M2") (pin "J1.11") (pinfunction "D8_J1.11") (pintype "bidirectional"))
    )
    (net (code "131") (name "unconnected-(M2-D9-PadJ1.12)") (class "Default")
      (node (ref "M2") (pin "J1.12") (pinfunction "D9_J1.12") (pintype "bidirectional"))
    )
    (net (code "132") (name "unconnected-(M2-D10-PadJ1.13)") (class "Default")
      (node (ref "M2") (pin "J1.13") (pinfunction "D10_J1.13") (pintype "bidirectional"))
    )
    (net (code "133") (name "unconnected-(M2-D11{slash}MOSI-PadJ1.14)") (class "Default")
      (node (ref "M2") (pin "J1.14") (pinfunction "D11/MOSI_J1.14") (pintype "bidirectional"))
    )
    (net (code "134") (name "unconnected-(M2-D12{slash}MISO-PadJ1.15)") (class "Default")
      (node (ref "M2") (pin "J1.15") (pinfunction "D12/MISO_J1.15") (pintype "bidirectional"))
    )
    (net (code "135") (name "unconnected-(M2-D13{slash}SCK-PadJ2.15)") (class "Default")
      (node (ref "M2") (pin "J2.15") (pinfunction "D13/SCK_J2.15") (pintype "bidirectional"))
    )
    (net (code "136") (name "unconnected-(M2-RST.2-PadJ2.3)") (class "Default")
      (node (ref "M2") (pin "J2.3") (pinfunction "RST.2_J2.3") (pintype "bidirectional"))
    )
  )
)
